# netzteil.net
KiCad netlist of a schematic drawn in EAGLE
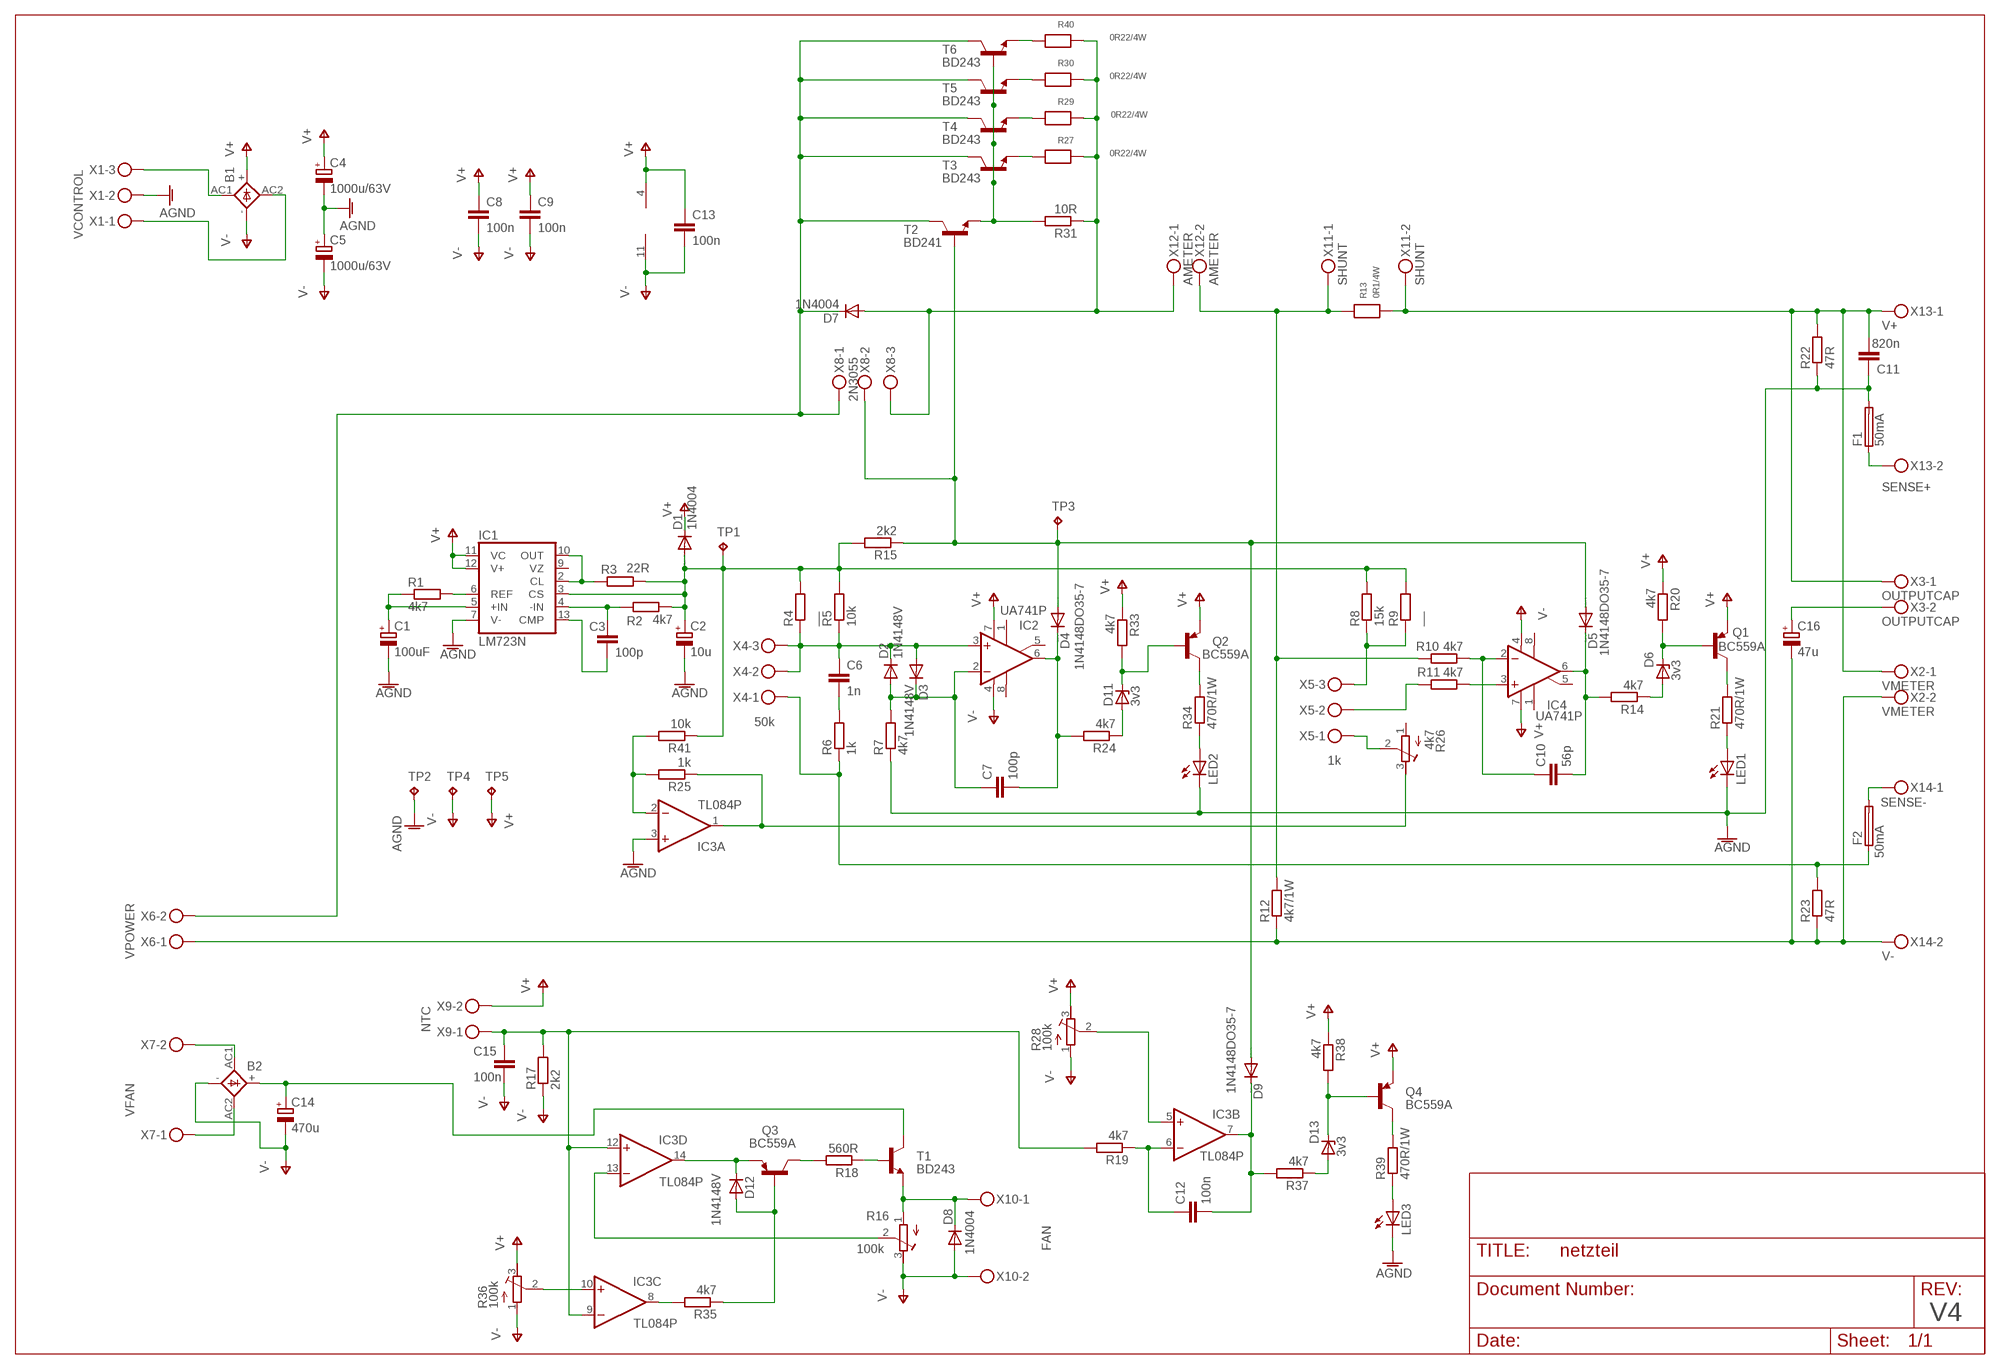
[diagram p0: schematic, sheet 1]

(export (version "E")
  (design (tool "Eeschema 10.0.6"))
  (components
    (comp (ref "B1")
      (value "1KAB")
      (footprint "eagle-import:1KAB")
      (libsource (lib "eagle-import") (part "1KAB"))
    )
    (comp (ref "B2")
      (value "1KAB")
      (footprint "eagle-import:1KAB")
      (libsource (lib "eagle-import") (part "1KAB"))
    )
    (comp (ref "C1")
      (value "100uF")
      (footprint "eagle-import:E3,5-8")
      (libsource (lib "eagle-import") (part "CPOL-EUE3.5-8"))
    )
    (comp (ref "C2")
      (value "10u")
      (footprint "eagle-import:E3,5-8")
      (libsource (lib "eagle-import") (part "CPOL-EUE3.5-8"))
    )
    (comp (ref "C3")
      (value "100p")
      (footprint "eagle-import:C025-025X050")
      (libsource (lib "eagle-import") (part "C-EU025-025X050"))
    )
    (comp (ref "C4")
      (value "1000u/63V")
      (footprint "eagle-import:E7,5-18")
      (libsource (lib "eagle-import") (part "CPOL-EUE7.5-18"))
    )
    (comp (ref "C5")
      (value "1000u/63V")
      (footprint "eagle-import:E7,5-18")
      (libsource (lib "eagle-import") (part "CPOL-EUE7.5-18"))
    )
    (comp (ref "C6")
      (value "1n")
      (footprint "eagle-import:C025-025X050")
      (libsource (lib "eagle-import") (part "C-EU025-025X050"))
    )
    (comp (ref "C7")
      (value "100p")
      (footprint "eagle-import:C025-025X050")
      (libsource (lib "eagle-import") (part "C-EU025-025X050"))
    )
    (comp (ref "C8")
      (value "100n")
      (footprint "eagle-import:C025-025X050")
      (libsource (lib "eagle-import") (part "C-EU025-025X050"))
    )
    (comp (ref "C9")
      (value "100n")
      (footprint "eagle-import:C025-025X050")
      (libsource (lib "eagle-import") (part "C-EU025-025X050"))
    )
    (comp (ref "C10")
      (value "56p")
      (footprint "eagle-import:C025-025X050")
      (libsource (lib "eagle-import") (part "C-EU025-025X050"))
    )
    (comp (ref "C11")
      (value "820n")
      (footprint "eagle-import:C025-025X050")
      (libsource (lib "eagle-import") (part "C-EU025-025X050"))
    )
    (comp (ref "C12")
      (value "100n")
      (footprint "eagle-import:C025-025X050")
      (libsource (lib "eagle-import") (part "C-EU025-025X050"))
    )
    (comp (ref "C13")
      (value "100n")
      (footprint "eagle-import:C025-025X050")
      (libsource (lib "eagle-import") (part "C-EU025-025X050"))
    )
    (comp (ref "C14")
      (value "470u")
      (footprint "eagle-import:E5-13")
      (libsource (lib "eagle-import") (part "CPOL-EUE5-13"))
    )
    (comp (ref "C15")
      (value "100n")
      (footprint "eagle-import:C025-025X050")
      (libsource (lib "eagle-import") (part "C-EU025-025X050"))
    )
    (comp (ref "C16")
      (value "47u")
      (footprint "eagle-import:E3,5-8")
      (libsource (lib "eagle-import") (part "CPOL-EUE3.5-8"))
    )
    (comp (ref "D1")
      (value "1N4004")
      (footprint "eagle-import:DO41-10")
      (libsource (lib "eagle-import") (part "diode_210_1N4004"))
    )
    (comp (ref "D2")
      (value "1N4148V")
      (footprint "eagle-import:SHORTDIODE")
      (libsource (lib "eagle-import") (part "1N4148V"))
    )
    (comp (ref "D3")
      (value "1N4148V")
      (footprint "eagle-import:SHORTDIODE")
      (libsource (lib "eagle-import") (part "1N4148V"))
    )
    (comp (ref "D4")
      (value "1N4148DO35-7")
      (footprint "eagle-import:DO35-7")
      (libsource (lib "eagle-import") (part "1N4148DO35-7"))
    )
    (comp (ref "D5")
      (value "1N4148DO35-7")
      (footprint "eagle-import:DO35-7")
      (libsource (lib "eagle-import") (part "1N4148DO35-7"))
    )
    (comp (ref "D6")
      (value "3v3")
      (footprint "eagle-import:SHORTDIODE")
      (libsource (lib "eagle-import") (part "ZENER-DIODE"))
    )
    (comp (ref "D7")
      (value "1N4004")
      (footprint "eagle-import:DO41-10")
      (libsource (lib "eagle-import") (part "1N4004"))
    )
    (comp (ref "D8")
      (value "1N4004")
      (footprint "eagle-import:DO41-10")
      (libsource (lib "eagle-import") (part "1N4004"))
    )
    (comp (ref "D9")
      (value "1N4148DO35-7")
      (footprint "eagle-import:DO35-7")
      (libsource (lib "eagle-import") (part "1N4148DO35-7"))
    )
    (comp (ref "D11")
      (value "3v3")
      (footprint "eagle-import:SHORTDIODE")
      (libsource (lib "eagle-import") (part "ZENER-DIODE"))
    )
    (comp (ref "D12")
      (value "1N4148V")
      (footprint "eagle-import:SHORTDIODE")
      (libsource (lib "eagle-import") (part "1N4148V"))
    )
    (comp (ref "D13")
      (value "3v3")
      (footprint "eagle-import:SHORTDIODE")
      (libsource (lib "eagle-import") (part "ZENER-DIODE"))
    )
    (comp (ref "F1")
      (value "50mA")
      (footprint "eagle-import:PICOFUSE")
      (libsource (lib "eagle-import") (part "FUSEPICOFUSE"))
    )
    (comp (ref "F2")
      (value "50mA")
      (footprint "eagle-import:PICOFUSE")
      (libsource (lib "eagle-import") (part "FUSEPICOFUSE"))
    )
    (comp (ref "IC1")
      (value "LM723N")
      (footprint "eagle-import:DIL14")
      (libsource (lib "eagle-import") (part "723NLM"))
    )
    (comp (ref "IC2")
      (value "UA741P")
      (footprint "eagle-import:DIL08")
      (libsource (lib "eagle-import") (part "741PUA"))
    )
    (comp (ref "IC3")
      (value "TL084P")
      (footprint "eagle-import:DIL14")
      (libsource (lib "eagle-import") (part "TL084P"))
    )
    (comp (ref "IC4")
      (value "UA741P")
      (footprint "eagle-import:DIL08")
      (libsource (lib "eagle-import") (part "741PUA"))
    )
    (comp (ref "LED1")
      (value "LED3MM")
      (footprint "eagle-import:LED3MM")
      (libsource (lib "eagle-import") (part "LED3MM"))
    )
    (comp (ref "LED2")
      (value "LED3MM")
      (footprint "eagle-import:LED3MM")
      (libsource (lib "eagle-import") (part "LED3MM"))
    )
    (comp (ref "LED3")
      (value "LED3MM")
      (footprint "eagle-import:LED3MM")
      (libsource (lib "eagle-import") (part "LED3MM"))
    )
    (comp (ref "Q1")
      (value "BC559A")
      (footprint "eagle-import:TO92-EBC")
      (libsource (lib "eagle-import") (part "BC559A"))
    )
    (comp (ref "Q2")
      (value "BC559A")
      (footprint "eagle-import:TO92-EBC")
      (libsource (lib "eagle-import") (part "BC559A"))
    )
    (comp (ref "Q3")
      (value "BC559A")
      (footprint "eagle-import:TO92-EBC")
      (libsource (lib "eagle-import") (part "BC559A"))
    )
    (comp (ref "Q4")
      (value "BC559A")
      (footprint "eagle-import:TO92-EBC")
      (libsource (lib "eagle-import") (part "BC559A"))
    )
    (comp (ref "R1")
      (value "4k7")
      (footprint "eagle-import:0207_2V")
      (libsource (lib "eagle-import") (part "R-EU_0207/2V"))
    )
    (comp (ref "R2")
      (value "4k7")
      (footprint "eagle-import:0207_2V")
      (libsource (lib "eagle-import") (part "R-EU_0207/2V"))
    )
    (comp (ref "R3")
      (value "22R")
      (footprint "eagle-import:0207_2V")
      (libsource (lib "eagle-import") (part "R-EU_0207/2V"))
    )
    (comp (ref "R4")
      (value "__")
      (footprint "eagle-import:0207_2V")
      (libsource (lib "eagle-import") (part "R-EU_0207/2V"))
    )
    (comp (ref "R5")
      (value "10k")
      (footprint "eagle-import:0207_2V")
      (libsource (lib "eagle-import") (part "R-EU_0207/2V"))
    )
    (comp (ref "R6")
      (value "1k")
      (footprint "eagle-import:0207_2V")
      (libsource (lib "eagle-import") (part "R-EU_0207/2V"))
    )
    (comp (ref "R7")
      (value "4k7")
      (footprint "eagle-import:0207_2V")
      (libsource (lib "eagle-import") (part "R-EU_0207/2V"))
    )
    (comp (ref "R8")
      (value "15k")
      (footprint "eagle-import:0207_2V")
      (libsource (lib "eagle-import") (part "R-EU_0207/2V"))
    )
    (comp (ref "R9")
      (value "__")
      (footprint "eagle-import:0207_2V")
      (libsource (lib "eagle-import") (part "R-EU_0207/2V"))
    )
    (comp (ref "R10")
      (value "4k7")
      (footprint "eagle-import:0207_2V")
      (libsource (lib "eagle-import") (part "R-EU_0207/2V"))
    )
    (comp (ref "R11")
      (value "4k7")
      (footprint "eagle-import:0207_2V")
      (libsource (lib "eagle-import") (part "R-EU_0207/2V"))
    )
    (comp (ref "R12")
      (value "4k7/1W")
      (footprint "eagle-import:0207_10")
      (libsource (lib "eagle-import") (part "R-EU_0207/10"))
    )
    (comp (ref "R13")
      (value "0R1/4W")
      (footprint "eagle-import:4W_RM15")
      (libsource (lib "eagle-import") (part "R"))
    )
    (comp (ref "R14")
      (value "4k7")
      (footprint "eagle-import:0207_2V")
      (libsource (lib "eagle-import") (part "R-EU_0207/2V"))
    )
    (comp (ref "R15")
      (value "2k2")
      (footprint "eagle-import:0207_7")
      (libsource (lib "eagle-import") (part "R-EU_0207/7"))
    )
    (comp (ref "R16")
      (value "100k")
      (footprint "eagle-import:RTRIM3296Y")
      (libsource (lib "eagle-import") (part "R-TRIMM3296Y"))
    )
    (comp (ref "R17")
      (value "2k2")
      (footprint "eagle-import:0207_2V")
      (libsource (lib "eagle-import") (part "R-EU_0207/2V"))
    )
    (comp (ref "R18")
      (value "560R")
      (footprint "eagle-import:0207_2V")
      (libsource (lib "eagle-import") (part "R-EU_0207/2V"))
    )
    (comp (ref "R19")
      (value "4k7")
      (footprint "eagle-import:0207_7")
      (libsource (lib "eagle-import") (part "R-EU_0207/7"))
    )
    (comp (ref "R20")
      (value "4k7")
      (footprint "eagle-import:0207_2V")
      (libsource (lib "eagle-import") (part "R-EU_0207/2V"))
    )
    (comp (ref "R21")
      (value "470R/1W")
      (footprint "eagle-import:0207_2V")
      (libsource (lib "eagle-import") (part "R-EU_0207/2V"))
    )
    (comp (ref "R22")
      (value "47R")
      (footprint "eagle-import:0207_2V")
      (libsource (lib "eagle-import") (part "R-EU_0207/2V"))
    )
    (comp (ref "R23")
      (value "47R")
      (footprint "eagle-import:0207_2V")
      (libsource (lib "eagle-import") (part "R-EU_0207/2V"))
    )
    (comp (ref "R24")
      (value "4k7")
      (footprint "eagle-import:0207_2V")
      (libsource (lib "eagle-import") (part "R-EU_0207/2V"))
    )
    (comp (ref "R25")
      (value "1k")
      (footprint "eagle-import:0207_2V")
      (libsource (lib "eagle-import") (part "R-EU_0207/2V"))
    )
    (comp (ref "R26")
      (value "4k7")
      (footprint "eagle-import:RTRIM3296Y")
      (libsource (lib "eagle-import") (part "R-TRIMM3296Y"))
    )
    (comp (ref "R27")
      (value "0R22/4W")
      (footprint "eagle-import:4W_RM15")
      (libsource (lib "eagle-import") (part "R"))
    )
    (comp (ref "R28")
      (value "100k")
      (footprint "eagle-import:RTRIM3296Y")
      (libsource (lib "eagle-import") (part "R-TRIMM3296Y"))
    )
    (comp (ref "R29")
      (value "0R22/4W")
      (footprint "eagle-import:4W_RM15")
      (libsource (lib "eagle-import") (part "R"))
    )
    (comp (ref "R30")
      (value "0R22/4W")
      (footprint "eagle-import:4W_RM15")
      (libsource (lib "eagle-import") (part "R"))
    )
    (comp (ref "R31")
      (value "10R")
      (footprint "eagle-import:0207_2V")
      (libsource (lib "eagle-import") (part "R-EU_0207/2V"))
    )
    (comp (ref "R33")
      (value "4k7")
      (footprint "eagle-import:0207_2V")
      (libsource (lib "eagle-import") (part "R-EU_0207/2V"))
    )
    (comp (ref "R34")
      (value "470R/1W")
      (footprint "eagle-import:0207_2V")
      (libsource (lib "eagle-import") (part "R-EU_0207/2V"))
    )
    (comp (ref "R35")
      (value "4k7")
      (footprint "eagle-import:0207_2V")
      (libsource (lib "eagle-import") (part "R-EU_0207/2V"))
    )
    (comp (ref "R36")
      (value "100k")
      (footprint "eagle-import:RTRIM3296Y")
      (libsource (lib "eagle-import") (part "R-TRIMM3296Y"))
    )
    (comp (ref "R37")
      (value "4k7")
      (footprint "eagle-import:0207_2V")
      (libsource (lib "eagle-import") (part "R-EU_0207/2V"))
    )
    (comp (ref "R38")
      (value "4k7")
      (footprint "eagle-import:0207_2V")
      (libsource (lib "eagle-import") (part "R-EU_0207/2V"))
    )
    (comp (ref "R39")
      (value "470R/1W")
      (footprint "eagle-import:0207_2V")
      (libsource (lib "eagle-import") (part "R-EU_0207/2V"))
    )
    (comp (ref "R40")
      (value "0R22/4W")
      (footprint "eagle-import:4W_RM15")
      (libsource (lib "eagle-import") (part "R"))
    )
    (comp (ref "R41")
      (value "10k")
      (footprint "eagle-import:0207_2V")
      (libsource (lib "eagle-import") (part "R-EU_0207/2V"))
    )
    (comp (ref "T1")
      (value "BD243")
      (footprint "eagle-import:TO220V")
      (libsource (lib "eagle-import") (part "-NPN-TO220V"))
    )
    (comp (ref "T2")
      (value "BD241")
      (footprint "eagle-import:TO220V")
      (libsource (lib "eagle-import") (part "-NPN-TO220V"))
    )
    (comp (ref "T3")
      (value "BD243")
      (footprint "eagle-import:TO220V")
      (libsource (lib "eagle-import") (part "-NPN-TO220V"))
    )
    (comp (ref "T4")
      (value "BD243")
      (footprint "eagle-import:TO220V")
      (libsource (lib "eagle-import") (part "-NPN-TO220V"))
    )
    (comp (ref "T5")
      (value "BD243")
      (footprint "eagle-import:TO220V")
      (libsource (lib "eagle-import") (part "-NPN-TO220V"))
    )
    (comp (ref "T6")
      (value "BD243")
      (footprint "eagle-import:TO220V")
      (libsource (lib "eagle-import") (part "-NPN-TO220V"))
    )
    (comp (ref "TP1")
      (value "TPPAD1-13")
      (footprint "eagle-import:P1-13")
      (libsource (lib "eagle-import") (part "TPPAD1-13"))
    )
    (comp (ref "TP2")
      (value "TPPAD1-13")
      (footprint "eagle-import:P1-13")
      (libsource (lib "eagle-import") (part "TPPAD1-13"))
    )
    (comp (ref "TP3")
      (value "TPPAD1-13")
      (footprint "eagle-import:P1-13")
      (libsource (lib "eagle-import") (part "TPPAD1-13"))
    )
    (comp (ref "TP4")
      (value "TPPAD1-13")
      (footprint "eagle-import:P1-13")
      (libsource (lib "eagle-import") (part "TPPAD1-13"))
    )
    (comp (ref "TP5")
      (value "TPPAD1-13")
      (footprint "eagle-import:P1-13")
      (libsource (lib "eagle-import") (part "TPPAD1-13"))
    )
    (comp (ref "X1")
      (value "VCONTROL")
      (footprint "eagle-import:MKDSN1,5_3-5,08")
      (libsource (lib "eagle-import") (part "MKDSN1,5/3-5,08"))
    )
    (comp (ref "X2")
      (value "VMETER")
      (footprint "eagle-import:MKDSN1,5_2-5,08")
      (libsource (lib "eagle-import") (part "MKDSN1,5/2-5,08"))
    )
    (comp (ref "X3")
      (value "OUTPUTCAP")
      (footprint "eagle-import:MKDSN1,5_2-5,08")
      (libsource (lib "eagle-import") (part "MKDSN1,5/2-5,08"))
    )
    (comp (ref "X4")
      (value "50k")
      (footprint "eagle-import:MKDSN1,5_3-5,08")
      (libsource (lib "eagle-import") (part "MKDSN1,5/3-5,08"))
    )
    (comp (ref "X5")
      (value "1k")
      (footprint "eagle-import:MKDSN1,5_3-5,08")
      (libsource (lib "eagle-import") (part "MKDSN1,5/3-5,08"))
    )
    (comp (ref "X6")
      (value "VPOWER")
      (footprint "eagle-import:MKDSN1,5_2-5,08")
      (libsource (lib "eagle-import") (part "MKDSN1,5/2-5,08"))
    )
    (comp (ref "X7")
      (value "VFAN")
      (footprint "eagle-import:MKDSN1,5_2-5,08")
      (libsource (lib "eagle-import") (part "MKDSN1,5/2-5,08"))
    )
    (comp (ref "X8")
      (value "2N3055")
      (footprint "eagle-import:MKDSN1,5_3-5,08")
      (libsource (lib "eagle-import") (part "MKDSN1,5/3-5,08"))
    )
    (comp (ref "X9")
      (value "NTC")
      (footprint "eagle-import:MKDSN1,5_2-5,08")
      (libsource (lib "eagle-import") (part "MKDSN1,5/2-5,08"))
    )
    (comp (ref "X10")
      (value "FAN")
      (footprint "eagle-import:MKDSN1,5_2-5,08")
      (libsource (lib "eagle-import") (part "MKDSN1,5/2-5,08"))
    )
    (comp (ref "X11")
      (value "SHUNT")
      (footprint "eagle-import:MKDSN1,5_2-5,08")
      (libsource (lib "eagle-import") (part "MKDSN1,5/2-5,08"))
    )
    (comp (ref "X12")
      (value "AMETER")
      (footprint "eagle-import:MKDSN1,5_2-5,08")
      (libsource (lib "eagle-import") (part "MKDSN1,5/2-5,08"))
    )
    (comp (ref "X13")
      (value "V+")
      (footprint "eagle-import:MKDSN1,5_2-5,08")
      (libsource (lib "eagle-import") (part "MKDSN1,5/2-5,08"))
    )
    (comp (ref "X14")
      (value "V-")
      (footprint "eagle-import:MKDSN1,5_2-5,08")
      (libsource (lib "eagle-import") (part "MKDSN1,5/2-5,08"))
    )
  )
  (nets
    (net (code "1") (name "AGND") (class "Default")
      (node (ref "C1") (pin "-") (pinfunction "-_-") (pintype "passive"))
      (node (ref "C11") (pin "1") (pinfunction "1_1") (pintype "passive"))
      (node (ref "C2") (pin "-") (pinfunction "-_-") (pintype "passive"))
      (node (ref "C4") (pin "-") (pinfunction "-_-") (pintype "passive"))
      (node (ref "C5") (pin "+") (pinfunction "+_+") (pintype "passive"))
      (node (ref "F1") (pin "2") (pinfunction "2_2") (pintype "passive"))
      (node (ref "IC1") (pin "7") (pinfunction "V-_7") (pintype "input"))
      (node (ref "IC3") (pin "3") (pinfunction "+IN_3") (pintype "input"))
      (node (ref "LED1") (pin "K") (pinfunction "C_K") (pintype "passive"))
      (node (ref "LED2") (pin "K") (pinfunction "C_K") (pintype "passive"))
      (node (ref "LED3") (pin "K") (pinfunction "C_K") (pintype "passive"))
      (node (ref "R22") (pin "1") (pinfunction "1_1") (pintype "passive"))
      (node (ref "R7") (pin "1") (pinfunction "1_1") (pintype "passive"))
      (node (ref "TP2") (pin "TP") (pinfunction "TP_TP") (pintype "input"))
      (node (ref "X1") (pin "2") (pinfunction "KL_2") (pintype "passive"))
    )
    (net (code "2") (name "Net-(C6-Pad2)") (class "Default")
      (node (ref "C6") (pin "2") (pinfunction "2_2") (pintype "passive"))
      (node (ref "R6") (pin "2") (pinfunction "2_2") (pintype "passive"))
    )
    (net (code "3") (name "Net-(D2-C)") (class "Default")
      (node (ref "C6") (pin "1") (pinfunction "1_1") (pintype "passive"))
      (node (ref "D2") (pin "K") (pinfunction "C_K") (pintype "passive"))
      (node (ref "D3") (pin "A") (pinfunction "A_A") (pintype "passive"))
      (node (ref "IC2") (pin "3") (pinfunction "+IN_3") (pintype "input"))
      (node (ref "R4") (pin "1") (pinfunction "1_1") (pintype "passive"))
      (node (ref "R5") (pin "1") (pinfunction "1_1") (pintype "passive"))
      (node (ref "X4") (pin "2") (pinfunction "KL_2") (pintype "passive"))
      (node (ref "X4") (pin "3") (pinfunction "KL_3") (pintype "passive"))
    )
    (net (code "4") (name "Net-(D3-C)") (class "Default")
      (node (ref "C7") (pin "1") (pinfunction "1_1") (pintype "passive"))
      (node (ref "D2") (pin "A") (pinfunction "A_A") (pintype "passive"))
      (node (ref "D3") (pin "K") (pinfunction "C_K") (pintype "passive"))
      (node (ref "IC2") (pin "2") (pinfunction "-IN_2") (pintype "input"))
      (node (ref "R7") (pin "2") (pinfunction "2_2") (pintype "passive"))
    )
    (net (code "5") (name "Net-(D6-C)") (class "Default")
      (node (ref "D6") (pin "K") (pinfunction "C_K") (pintype "passive"))
      (node (ref "Q1") (pin "B") (pinfunction "B_B") (pintype "passive"))
      (node (ref "R20") (pin "2") (pinfunction "2_2") (pintype "passive"))
    )
    (net (code "6") (name "Net-(D6-PadA)") (class "Default")
      (node (ref "D6") (pin "A") (pinfunction "A_A") (pintype "passive"))
      (node (ref "R14") (pin "1") (pinfunction "1_1") (pintype "passive"))
    )
    (net (code "7") (name "Net-(D11-C)") (class "Default")
      (node (ref "D11") (pin "K") (pinfunction "C_K") (pintype "passive"))
      (node (ref "Q2") (pin "B") (pinfunction "B_B") (pintype "passive"))
      (node (ref "R33") (pin "2") (pinfunction "2_2") (pintype "passive"))
    )
    (net (code "8") (name "Net-(D11-PadA)") (class "Default")
      (node (ref "D11") (pin "A") (pinfunction "A_A") (pintype "passive"))
      (node (ref "R24") (pin "1") (pinfunction "1_1") (pintype "passive"))
    )
    (net (code "9") (name "Net-(D12-C)") (class "Default")
      (node (ref "D12") (pin "K") (pinfunction "C_K") (pintype "passive"))
      (node (ref "IC3") (pin "14") (pinfunction "OUT_14") (pintype "output"))
      (node (ref "Q3") (pin "E") (pinfunction "E_E") (pintype "passive"))
    )
    (net (code "10") (name "Net-(D12-PadA)") (class "Default")
      (node (ref "D12") (pin "A") (pinfunction "A_A") (pintype "passive"))
      (node (ref "Q3") (pin "B") (pinfunction "B_B") (pintype "passive"))
      (node (ref "R35") (pin "1") (pinfunction "1_1") (pintype "passive"))
    )
    (net (code "11") (name "Net-(D13-C)") (class "Default")
      (node (ref "D13") (pin "K") (pinfunction "C_K") (pintype "passive"))
      (node (ref "Q4") (pin "B") (pinfunction "B_B") (pintype "passive"))
      (node (ref "R38") (pin "2") (pinfunction "2_2") (pintype "passive"))
    )
    (net (code "12") (name "Net-(D13-PadA)") (class "Default")
      (node (ref "D13") (pin "A") (pinfunction "A_A") (pintype "passive"))
      (node (ref "R37") (pin "1") (pinfunction "1_1") (pintype "passive"))
    )
    (net (code "13") (name "Net-(IC1-+IN)") (class "Default")
      (node (ref "C1") (pin "+") (pinfunction "+_+") (pintype "passive"))
      (node (ref "IC1") (pin "5") (pinfunction "+IN_5") (pintype "input"))
      (node (ref "R1") (pin "1") (pinfunction "1_1") (pintype "passive"))
    )
    (net (code "14") (name "Net-(IC1--IN)") (class "Default")
      (node (ref "C3") (pin "1") (pinfunction "1_1") (pintype "passive"))
      (node (ref "IC1") (pin "4") (pinfunction "-IN_4") (pintype "input"))
      (node (ref "R2") (pin "1") (pinfunction "1_1") (pintype "passive"))
    )
    (net (code "15") (name "Net-(IC1-CL)") (class "Default")
      (node (ref "IC1") (pin "10") (pinfunction "OUT_10") (pintype "output"))
      (node (ref "IC1") (pin "2") (pinfunction "CL_2") (pintype "input"))
      (node (ref "R3") (pin "1") (pinfunction "1_1") (pintype "passive"))
    )
    (net (code "16") (name "Net-(IC1-CMP)") (class "Default")
      (node (ref "C3") (pin "2") (pinfunction "2_2") (pintype "passive"))
      (node (ref "IC1") (pin "13") (pinfunction "CMP_13") (pintype "passive"))
    )
    (net (code "17") (name "Net-(IC1-CS)") (class "Default")
      (node (ref "C2") (pin "+") (pinfunction "+_+") (pintype "passive"))
      (node (ref "D1") (pin "A") (pinfunction "A_A") (pintype "passive"))
      (node (ref "IC1") (pin "3") (pinfunction "CS_3") (pintype "input"))
      (node (ref "R15") (pin "2") (pinfunction "2_2") (pintype "passive"))
      (node (ref "R2") (pin "2") (pinfunction "2_2") (pintype "passive"))
      (node (ref "R3") (pin "2") (pinfunction "2_2") (pintype "passive"))
      (node (ref "R4") (pin "2") (pinfunction "2_2") (pintype "passive"))
      (node (ref "R41") (pin "1") (pinfunction "1_1") (pintype "passive"))
      (node (ref "R5") (pin "2") (pinfunction "2_2") (pintype "passive"))
      (node (ref "R8") (pin "2") (pinfunction "2_2") (pintype "passive"))
      (node (ref "R9") (pin "2") (pinfunction "2_2") (pintype "passive"))
      (node (ref "TP1") (pin "TP") (pinfunction "TP_TP") (pintype "input"))
    )
    (net (code "18") (name "Net-(IC1-REF)") (class "Default")
      (node (ref "IC1") (pin "6") (pinfunction "REF_6") (pintype "output"))
      (node (ref "R1") (pin "2") (pinfunction "2_2") (pintype "passive"))
    )
    (net (code "19") (name "Net-(IC2-OUT)") (class "Default")
      (node (ref "C7") (pin "2") (pinfunction "2_2") (pintype "passive"))
      (node (ref "D4") (pin "C") (pinfunction "C_C") (pintype "passive"))
      (node (ref "IC2") (pin "6") (pinfunction "OUT_6") (pintype "output"))
      (node (ref "R24") (pin "2") (pinfunction "2_2") (pintype "passive"))
    )
    (net (code "20") (name "Net-(IC3A--IN)") (class "Default")
      (node (ref "IC3") (pin "2") (pinfunction "-IN_2") (pintype "input"))
      (node (ref "R25") (pin "2") (pinfunction "2_2") (pintype "passive"))
      (node (ref "R41") (pin "2") (pinfunction "2_2") (pintype "passive"))
    )
    (net (code "21") (name "Net-(IC3A-OUT)") (class "Default")
      (node (ref "IC3") (pin "1") (pinfunction "OUT_1") (pintype "output"))
      (node (ref "R25") (pin "1") (pinfunction "1_1") (pintype "passive"))
      (node (ref "R26") (pin "3") (pinfunction "E_3") (pintype "passive"))
    )
    (net (code "22") (name "Net-(IC3B-+IN)") (class "Default")
      (node (ref "IC3") (pin "5") (pinfunction "+IN_5") (pintype "input"))
      (node (ref "R28") (pin "2") (pinfunction "S_2") (pintype "passive"))
    )
    (net (code "23") (name "Net-(IC3B--IN)") (class "Default")
      (node (ref "C12") (pin "1") (pinfunction "1_1") (pintype "passive"))
      (node (ref "IC3") (pin "6") (pinfunction "-IN_6") (pintype "input"))
      (node (ref "R19") (pin "1") (pinfunction "1_1") (pintype "passive"))
    )
    (net (code "24") (name "Net-(IC3B-OUT)") (class "Default")
      (node (ref "C12") (pin "2") (pinfunction "2_2") (pintype "passive"))
      (node (ref "D9") (pin "C") (pinfunction "C_C") (pintype "passive"))
      (node (ref "IC3") (pin "7") (pinfunction "OUT_7") (pintype "output"))
      (node (ref "R37") (pin "2") (pinfunction "2_2") (pintype "passive"))
    )
    (net (code "25") (name "Net-(IC3C-+IN)") (class "Default")
      (node (ref "IC3") (pin "10") (pinfunction "+IN_10") (pintype "input"))
      (node (ref "R36") (pin "2") (pinfunction "S_2") (pintype "passive"))
    )
    (net (code "26") (name "Net-(IC3C--IN)") (class "Default")
      (node (ref "C15") (pin "1") (pinfunction "1_1") (pintype "passive"))
      (node (ref "IC3") (pin "12") (pinfunction "+IN_12") (pintype "input"))
      (node (ref "IC3") (pin "9") (pinfunction "-IN_9") (pintype "input"))
      (node (ref "R17") (pin "2") (pinfunction "2_2") (pintype "passive"))
      (node (ref "R19") (pin "2") (pinfunction "2_2") (pintype "passive"))
      (node (ref "X9") (pin "1") (pinfunction "KL_1") (pintype "passive"))
    )
    (net (code "27") (name "Net-(IC3C-OUT)") (class "Default")
      (node (ref "IC3") (pin "8") (pinfunction "OUT_8") (pintype "output"))
      (node (ref "R35") (pin "2") (pinfunction "2_2") (pintype "passive"))
    )
    (net (code "28") (name "Net-(IC3D--IN)") (class "Default")
      (node (ref "IC3") (pin "13") (pinfunction "-IN_13") (pintype "input"))
      (node (ref "R16") (pin "2") (pinfunction "S_2") (pintype "passive"))
    )
    (net (code "29") (name "Net-(IC4-+IN)") (class "Default")
      (node (ref "IC4") (pin "3") (pinfunction "+IN_3") (pintype "input"))
      (node (ref "R11") (pin "1") (pinfunction "1_1") (pintype "passive"))
    )
    (net (code "30") (name "Net-(IC4--IN)") (class "Default")
      (node (ref "C10") (pin "1") (pinfunction "1_1") (pintype "passive"))
      (node (ref "IC4") (pin "2") (pinfunction "-IN_2") (pintype "input"))
      (node (ref "R10") (pin "1") (pinfunction "1_1") (pintype "passive"))
    )
    (net (code "31") (name "Net-(IC4-OUT)") (class "Default")
      (node (ref "C10") (pin "2") (pinfunction "2_2") (pintype "passive"))
      (node (ref "D5") (pin "C") (pinfunction "C_C") (pintype "passive"))
      (node (ref "IC4") (pin "6") (pinfunction "OUT_6") (pintype "output"))
      (node (ref "R14") (pin "2") (pinfunction "2_2") (pintype "passive"))
    )
    (net (code "32") (name "Net-(LED1-PadA)") (class "Default")
      (node (ref "LED1") (pin "A") (pinfunction "A_A") (pintype "passive"))
      (node (ref "R21") (pin "1") (pinfunction "1_1") (pintype "passive"))
    )
    (net (code "33") (name "Net-(LED2-PadA)") (class "Default")
      (node (ref "LED2") (pin "A") (pinfunction "A_A") (pintype "passive"))
      (node (ref "R34") (pin "1") (pinfunction "1_1") (pintype "passive"))
    )
    (net (code "34") (name "Net-(LED3-PadA)") (class "Default")
      (node (ref "LED3") (pin "A") (pinfunction "A_A") (pintype "passive"))
      (node (ref "R39") (pin "1") (pinfunction "1_1") (pintype "passive"))
    )
    (net (code "35") (name "Net-(Q1-PadC)") (class "Default")
      (node (ref "Q1") (pin "C") (pinfunction "C_C") (pintype "passive"))
      (node (ref "R21") (pin "2") (pinfunction "2_2") (pintype "passive"))
    )
    (net (code "36") (name "Net-(Q2-PadC)") (class "Default")
      (node (ref "Q2") (pin "C") (pinfunction "C_C") (pintype "passive"))
      (node (ref "R34") (pin "2") (pinfunction "2_2") (pintype "passive"))
    )
    (net (code "37") (name "Net-(Q3-PadC)") (class "Default")
      (node (ref "Q3") (pin "C") (pinfunction "C_C") (pintype "passive"))
      (node (ref "R18") (pin "2") (pinfunction "2_2") (pintype "passive"))
    )
    (net (code "38") (name "Net-(Q4-PadC)") (class "Default")
      (node (ref "Q4") (pin "C") (pinfunction "C_C") (pintype "passive"))
      (node (ref "R39") (pin "2") (pinfunction "2_2") (pintype "passive"))
    )
    (net (code "39") (name "Net-(R16-A)") (class "Default")
      (node (ref "D8") (pin "C") (pinfunction "C_C") (pintype "passive"))
      (node (ref "R16") (pin "1") (pinfunction "A_1") (pintype "passive"))
      (node (ref "T1") (pin "3") (pinfunction "E_3") (pintype "passive"))
      (node (ref "X10") (pin "1") (pinfunction "KL_1") (pintype "passive"))
    )
    (net (code "40") (name "Net-(R26-S)") (class "Default")
      (node (ref "R26") (pin "2") (pinfunction "S_2") (pintype "passive"))
      (node (ref "X5") (pin "1") (pinfunction "KL_1") (pintype "passive"))
    )
    (net (code "41") (name "Net-(T1-B)") (class "Default")
      (node (ref "R18") (pin "1") (pinfunction "1_1") (pintype "passive"))
      (node (ref "T1") (pin "1") (pinfunction "B_1") (pintype "passive"))
    )
    (net (code "42") (name "Net-(T1-C)") (class "Default")
      (node (ref "B2") (pin "+") (pinfunction "+_+") (pintype "passive"))
      (node (ref "C14") (pin "+") (pinfunction "+_+") (pintype "passive"))
      (node (ref "T1") (pin "2") (pinfunction "C_2") (pintype "passive"))
    )
    (net (code "43") (name "Net-(T2-B)") (class "Default")
      (node (ref "D4") (pin "A") (pinfunction "A_A") (pintype "passive"))
      (node (ref "D5") (pin "A") (pinfunction "A_A") (pintype "passive"))
      (node (ref "D9") (pin "A") (pinfunction "A_A") (pintype "passive"))
      (node (ref "R15") (pin "1") (pinfunction "1_1") (pintype "passive"))
      (node (ref "T2") (pin "1") (pinfunction "B_1") (pintype "passive"))
      (node (ref "TP3") (pin "TP") (pinfunction "TP_TP") (pintype "input"))
      (node (ref "X8") (pin "2") (pinfunction "KL_2") (pintype "passive"))
    )
    (net (code "44") (name "Net-(T2-C)") (class "Default")
      (node (ref "D7") (pin "C") (pinfunction "C_C") (pintype "passive"))
      (node (ref "T2") (pin "2") (pinfunction "C_2") (pintype "passive"))
      (node (ref "T3") (pin "2") (pinfunction "C_2") (pintype "passive"))
      (node (ref "T4") (pin "2") (pinfunction "C_2") (pintype "passive"))
      (node (ref "T5") (pin "2") (pinfunction "C_2") (pintype "passive"))
      (node (ref "T6") (pin "2") (pinfunction "C_2") (pintype "passive"))
      (node (ref "X6") (pin "2") (pinfunction "KL_2") (pintype "passive"))
      (node (ref "X8") (pin "1") (pinfunction "KL_1") (pintype "passive"))
    )
    (net (code "45") (name "Net-(T2-E)") (class "Default")
      (node (ref "R31") (pin "2") (pinfunction "2_2") (pintype "passive"))
      (node (ref "T2") (pin "3") (pinfunction "E_3") (pintype "passive"))
      (node (ref "T3") (pin "1") (pinfunction "B_1") (pintype "passive"))
      (node (ref "T4") (pin "1") (pinfunction "B_1") (pintype "passive"))
      (node (ref "T5") (pin "1") (pinfunction "B_1") (pintype "passive"))
      (node (ref "T6") (pin "1") (pinfunction "B_1") (pintype "passive"))
    )
    (net (code "46") (name "Net-(T3-E)") (class "Default")
      (node (ref "R27") (pin "P$1") (pinfunction "P$1_P$1") (pintype "bidirectional"))
      (node (ref "T3") (pin "3") (pinfunction "E_3") (pintype "passive"))
    )
    (net (code "47") (name "Net-(T4-E)") (class "Default")
      (node (ref "R29") (pin "P$1") (pinfunction "P$1_P$1") (pintype "bidirectional"))
      (node (ref "T4") (pin "3") (pinfunction "E_3") (pintype "passive"))
    )
    (net (code "48") (name "Net-(T5-E)") (class "Default")
      (node (ref "R30") (pin "P$1") (pinfunction "P$1_P$1") (pintype "bidirectional"))
      (node (ref "T5") (pin "3") (pinfunction "E_3") (pintype "passive"))
    )
    (net (code "49") (name "Net-(T6-E)") (class "Default")
      (node (ref "R40") (pin "P$1") (pinfunction "P$1_P$1") (pintype "bidirectional"))
      (node (ref "T6") (pin "3") (pinfunction "E_3") (pintype "passive"))
    )
    (net (code "50") (name "Net-(X1A-KL)") (class "Default")
      (node (ref "B1") (pin "AC2") (pinfunction "AC2_AC2") (pintype "passive"))
      (node (ref "X1") (pin "1") (pinfunction "KL_1") (pintype "passive"))
    )
    (net (code "51") (name "Net-(X1C-KL)") (class "Default")
      (node (ref "B1") (pin "AC1") (pinfunction "AC1_AC1") (pintype "passive"))
      (node (ref "X1") (pin "3") (pinfunction "KL_3") (pintype "passive"))
    )
    (net (code "52") (name "Net-(X3B-KL)") (class "Default")
      (node (ref "C16") (pin "+") (pinfunction "+_+") (pintype "passive"))
      (node (ref "X3") (pin "2") (pinfunction "KL_2") (pintype "passive"))
    )
    (net (code "53") (name "Net-(X4A-KL)") (class "Default")
      (node (ref "F2") (pin "1") (pinfunction "1_1") (pintype "passive"))
      (node (ref "R23") (pin "2") (pinfunction "2_2") (pintype "passive"))
      (node (ref "R6") (pin "1") (pinfunction "1_1") (pintype "passive"))
      (node (ref "X4") (pin "1") (pinfunction "KL_1") (pintype "passive"))
    )
    (net (code "54") (name "Net-(X5B-KL)") (class "Default")
      (node (ref "R11") (pin "2") (pinfunction "2_2") (pintype "passive"))
      (node (ref "X5") (pin "2") (pinfunction "KL_2") (pintype "passive"))
    )
    (net (code "55") (name "Net-(X5C-KL)") (class "Default")
      (node (ref "R8") (pin "1") (pinfunction "1_1") (pintype "passive"))
      (node (ref "R9") (pin "1") (pinfunction "1_1") (pintype "passive"))
      (node (ref "X5") (pin "3") (pinfunction "KL_3") (pintype "passive"))
    )
    (net (code "56") (name "Net-(X7A-KL)") (class "Default")
      (node (ref "B2") (pin "AC2") (pinfunction "AC2_AC2") (pintype "passive"))
      (node (ref "X7") (pin "1") (pinfunction "KL_1") (pintype "passive"))
    )
    (net (code "57") (name "Net-(X7B-KL)") (class "Default")
      (node (ref "B2") (pin "AC1") (pinfunction "AC1_AC1") (pintype "passive"))
      (node (ref "X7") (pin "2") (pinfunction "KL_2") (pintype "passive"))
    )
    (net (code "58") (name "Net-(X11A-KL)") (class "Default")
      (node (ref "R10") (pin "2") (pinfunction "2_2") (pintype "passive"))
      (node (ref "R12") (pin "2") (pinfunction "2_2") (pintype "passive"))
      (node (ref "R13") (pin "P$1") (pinfunction "P$1_P$1") (pintype "bidirectional"))
      (node (ref "X11") (pin "1") (pinfunction "KL_1") (pintype "passive"))
      (node (ref "X12") (pin "2") (pinfunction "KL_2") (pintype "passive"))
    )
    (net (code "59") (name "Net-(X11B-KL)") (class "Default")
      (node (ref "C11") (pin "2") (pinfunction "2_2") (pintype "passive"))
      (node (ref "R13") (pin "P$2") (pinfunction "P$2_P$2") (pintype "bidirectional"))
      (node (ref "R22") (pin "2") (pinfunction "2_2") (pintype "passive"))
      (node (ref "X11") (pin "2") (pinfunction "KL_2") (pintype "passive"))
      (node (ref "X13") (pin "1") (pinfunction "KL_1") (pintype "passive"))
      (node (ref "X2") (pin "1") (pinfunction "KL_1") (pintype "passive"))
      (node (ref "X3") (pin "1") (pinfunction "KL_1") (pintype "passive"))
    )
    (net (code "60") (name "Net-(X12A-KL)") (class "Default")
      (node (ref "D7") (pin "A") (pinfunction "A_A") (pintype "passive"))
      (node (ref "R27") (pin "P$2") (pinfunction "P$2_P$2") (pintype "bidirectional"))
      (node (ref "R29") (pin "P$2") (pinfunction "P$2_P$2") (pintype "bidirectional"))
      (node (ref "R30") (pin "P$2") (pinfunction "P$2_P$2") (pintype "bidirectional"))
      (node (ref "R31") (pin "1") (pinfunction "1_1") (pintype "passive"))
      (node (ref "R40") (pin "P$2") (pinfunction "P$2_P$2") (pintype "bidirectional"))
      (node (ref "X12") (pin "1") (pinfunction "KL_1") (pintype "passive"))
      (node (ref "X8") (pin "3") (pinfunction "KL_3") (pintype "passive"))
    )
    (net (code "61") (name "Net-(X13B-KL)") (class "Default")
      (node (ref "F1") (pin "1") (pinfunction "1_1") (pintype "passive"))
      (node (ref "X13") (pin "2") (pinfunction "KL_2") (pintype "passive"))
    )
    (net (code "62") (name "Net-(X14A-KL)") (class "Default")
      (node (ref "F2") (pin "2") (pinfunction "2_2") (pintype "passive"))
      (node (ref "X14") (pin "1") (pinfunction "KL_1") (pintype "passive"))
    )
    (net (code "63") (name "Net-(X14B-KL)") (class "Default")
      (node (ref "C16") (pin "-") (pinfunction "-_-") (pintype "passive"))
      (node (ref "R12") (pin "1") (pinfunction "1_1") (pintype "passive"))
      (node (ref "R23") (pin "1") (pinfunction "1_1") (pintype "passive"))
      (node (ref "X14") (pin "2") (pinfunction "KL_2") (pintype "passive"))
      (node (ref "X2") (pin "2") (pinfunction "KL_2") (pintype "passive"))
      (node (ref "X6") (pin "1") (pinfunction "KL_1") (pintype "passive"))
    )
    (net (code "64") (name "V+") (class "Default")
      (node (ref "B1") (pin "+") (pinfunction "+_+") (pintype "passive"))
      (node (ref "C13") (pin "1") (pinfunction "1_1") (pintype "passive"))
      (node (ref "C4") (pin "+") (pinfunction "+_+") (pintype "passive"))
      (node (ref "C8") (pin "1") (pinfunction "1_1") (pintype "passive"))
      (node (ref "C9") (pin "1") (pinfunction "1_1") (pintype "passive"))
      (node (ref "D1") (pin "C") (pinfunction "C_C") (pintype "passive"))
      (node (ref "IC1") (pin "11") (pinfunction "VC_11") (pintype "input"))
      (node (ref "IC1") (pin "12") (pinfunction "V+_12") (pintype "input"))
      (node (ref "IC2") (pin "7") (pinfunction "V+_7") (pintype "power_in"))
      (node (ref "IC3") (pin "4") (pinfunction "V+_4") (pintype "power_in"))
      (node (ref "IC4") (pin "7") (pinfunction "V+_7") (pintype "power_in"))
      (node (ref "Q1") (pin "E") (pinfunction "E_E") (pintype "passive"))
      (node (ref "Q2") (pin "E") (pinfunction "E_E") (pintype "passive"))
      (node (ref "Q4") (pin "E") (pinfunction "E_E") (pintype "passive"))
      (node (ref "R20") (pin "1") (pinfunction "1_1") (pintype "passive"))
      (node (ref "R28") (pin "3") (pinfunction "E_3") (pintype "passive"))
      (node (ref "R33") (pin "1") (pinfunction "1_1") (pintype "passive"))
      (node (ref "R36") (pin "3") (pinfunction "E_3") (pintype "passive"))
      (node (ref "R38") (pin "1") (pinfunction "1_1") (pintype "passive"))
      (node (ref "TP5") (pin "TP") (pinfunction "TP_TP") (pintype "input"))
      (node (ref "X9") (pin "2") (pinfunction "KL_2") (pintype "passive"))
    )
    (net (code "65") (name "V-") (class "Default")
      (node (ref "B1") (pin "-") (pinfunction "-_-") (pintype "passive"))
      (node (ref "B2") (pin "-") (pinfunction "-_-") (pintype "passive"))
      (node (ref "C13") (pin "2") (pinfunction "2_2") (pintype "passive"))
      (node (ref "C14") (pin "-") (pinfunction "-_-") (pintype "passive"))
      (node (ref "C15") (pin "2") (pinfunction "2_2") (pintype "passive"))
      (node (ref "C5") (pin "-") (pinfunction "-_-") (pintype "passive"))
      (node (ref "C8") (pin "2") (pinfunction "2_2") (pintype "passive"))
      (node (ref "C9") (pin "2") (pinfunction "2_2") (pintype "passive"))
      (node (ref "D8") (pin "A") (pinfunction "A_A") (pintype "passive"))
      (node (ref "IC2") (pin "4") (pinfunction "V-_4") (pintype "power_in"))
      (node (ref "IC3") (pin "11") (pinfunction "V-_11") (pintype "power_in"))
      (node (ref "IC4") (pin "4") (pinfunction "V-_4") (pintype "power_in"))
      (node (ref "R16") (pin "3") (pinfunction "E_3") (pintype "passive"))
      (node (ref "R17") (pin "1") (pinfunction "1_1") (pintype "passive"))
      (node (ref "R28") (pin "1") (pinfunction "A_1") (pintype "passive"))
      (node (ref "R36") (pin "1") (pinfunction "A_1") (pintype "passive"))
      (node (ref "TP4") (pin "TP") (pinfunction "TP_TP") (pintype "input"))
      (node (ref "X10") (pin "2") (pinfunction "KL_2") (pintype "passive"))
    )
    (net (code "66") (name "unconnected-(IC1-VZ-Pad9)") (class "Default")
      (node (ref "IC1") (pin "9") (pinfunction "VZ_9") (pintype "output"))
    )
    (net (code "67") (name "unconnected-(IC2-ON1-Pad1)") (class "Default")
      (node (ref "IC2") (pin "1") (pinfunction "ON1_1") (pintype "passive"))
    )
    (net (code "68") (name "unconnected-(IC2-ON2-Pad5)") (class "Default")
      (node (ref "IC2") (pin "5") (pinfunction "ON2_5") (pintype "passive"))
    )
    (net (code "69") (name "unconnected-(IC2-OPT-Pad8)") (class "Default")
      (node (ref "IC2") (pin "8") (pinfunction "OPT_8") (pintype "passive"))
    )
    (net (code "70") (name "unconnected-(IC4-ON1-Pad1)") (class "Default")
      (node (ref "IC4") (pin "1") (pinfunction "ON1_1") (pintype "passive"))
    )
    (net (code "71") (name "unconnected-(IC4-ON2-Pad5)") (class "Default")
      (node (ref "IC4") (pin "5") (pinfunction "ON2_5") (pintype "passive"))
    )
    (net (code "72") (name "unconnected-(IC4-OPT-Pad8)") (class "Default")
      (node (ref "IC4") (pin "8") (pinfunction "OPT_8") (pintype "passive"))
    )
    (net (code "73") (name "unconnected-(R26-A-Pad1)") (class "Default")
      (node (ref "R26") (pin "1") (pinfunction "A_1") (pintype "passive"))
    )
  )
)
